# Active_Sensor_BB.net
KiCad netlist of a schematic drawn in Altium Designer
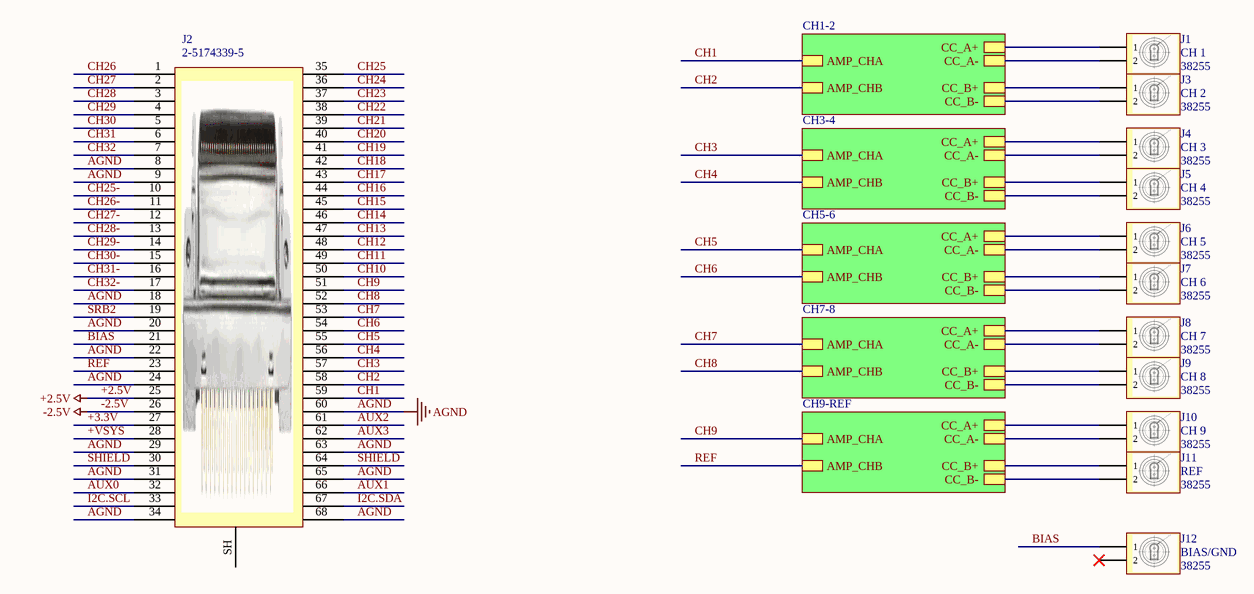
[diagram p0: Active Sensor BB.SchDoc]

(export (version "E")
  (design (tool "Eeschema 10.0.6"))
  (components
    (comp (ref "J1")
      (value "CH 1")
      (footprint "38255")
      (fields (field (name "MANUFACTURER") "PLASTICS1") (field (name "MANUFACTURER PART NUMBER") "38255"))
      (libsource (lib "CC BREAKOUT BOARD SCHLIB") (part "38255"))
    )
    (comp (ref "J2")
      (value "10268-6212PC")
      (footprint "2-5174339-5")
      (fields
        (field (name "MANUFACTURER") "TE Connectivity")
        (field (name "MANUFACTURER PART NUMBER") "2-5174339-5")
      )
      (libsource (lib "LUCHADOR SCHLIB") (part "10268-6212PC"))
    )
    (comp (ref "J3")
      (value "CH 2")
      (footprint "38255")
      (fields (field (name "MANUFACTURER") "PLASTICS1") (field (name "MANUFACTURER PART NUMBER") "38255"))
      (libsource (lib "CC BREAKOUT BOARD SCHLIB") (part "38255"))
    )
    (comp (ref "J4")
      (value "CH 3")
      (footprint "38255")
      (fields (field (name "MANUFACTURER") "PLASTICS1") (field (name "MANUFACTURER PART NUMBER") "38255"))
      (libsource (lib "CC BREAKOUT BOARD SCHLIB") (part "38255"))
    )
    (comp (ref "J5")
      (value "CH 4")
      (footprint "38255")
      (fields (field (name "MANUFACTURER") "PLASTICS1") (field (name "MANUFACTURER PART NUMBER") "38255"))
      (libsource (lib "CC BREAKOUT BOARD SCHLIB") (part "38255"))
    )
    (comp (ref "J6")
      (value "CH 5")
      (footprint "38255")
      (fields (field (name "MANUFACTURER") "PLASTICS1") (field (name "MANUFACTURER PART NUMBER") "38255"))
      (libsource (lib "CC BREAKOUT BOARD SCHLIB") (part "38255"))
    )
    (comp (ref "J7")
      (value "CH 6")
      (footprint "38255")
      (fields (field (name "MANUFACTURER") "PLASTICS1") (field (name "MANUFACTURER PART NUMBER") "38255"))
      (libsource (lib "CC BREAKOUT BOARD SCHLIB") (part "38255"))
    )
    (comp (ref "J8")
      (value "CH 7")
      (footprint "38255")
      (fields (field (name "MANUFACTURER") "PLASTICS1") (field (name "MANUFACTURER PART NUMBER") "38255"))
      (libsource (lib "CC BREAKOUT BOARD SCHLIB") (part "38255"))
    )
    (comp (ref "J9")
      (value "CH 8")
      (footprint "38255")
      (fields (field (name "MANUFACTURER") "PLASTICS1") (field (name "MANUFACTURER PART NUMBER") "38255"))
      (libsource (lib "CC BREAKOUT BOARD SCHLIB") (part "38255"))
    )
    (comp (ref "J10")
      (value "CH 9")
      (footprint "38255")
      (fields (field (name "MANUFACTURER") "PLASTICS1") (field (name "MANUFACTURER PART NUMBER") "38255"))
      (libsource (lib "CC BREAKOUT BOARD SCHLIB") (part "38255"))
    )
    (comp (ref "J11")
      (value "REF")
      (footprint "38255")
      (fields (field (name "MANUFACTURER") "PLASTICS1") (field (name "MANUFACTURER PART NUMBER") "38255"))
      (libsource (lib "CC BREAKOUT BOARD SCHLIB") (part "38255"))
    )
    (comp (ref "J12")
      (value "BIAS/GND")
      (footprint "38255")
      (fields (field (name "MANUFACTURER") "PLASTICS1") (field (name "MANUFACTURER PART NUMBER") "38255"))
      (libsource (lib "CC BREAKOUT BOARD SCHLIB") (part "38255"))
    )
  )
  (nets
    (net (code "1") (name "+2.5V") (class "Default")
      (node (ref "J2") (pin "25") (pinfunction "25_25") (pintype "passive"))
    )
    (net (code "2") (name "-2.5V") (class "Default")
      (node (ref "J2") (pin "26") (pinfunction "26_26") (pintype "passive"))
    )
    (net (code "3") (name "/+3.3V") (class "Default")
      (node (ref "J2") (pin "27") (pinfunction "27_27") (pintype "passive"))
    )
    (net (code "4") (name "/+VSYS") (class "Default")
      (node (ref "J2") (pin "28") (pinfunction "28_28") (pintype "passive"))
    )
    (net (code "5") (name "/AUX0") (class "Default")
      (node (ref "J2") (pin "32") (pinfunction "32_32") (pintype "passive"))
    )
    (net (code "6") (name "/AUX1") (class "Default")
      (node (ref "J2") (pin "66") (pinfunction "66_66") (pintype "passive"))
    )
    (net (code "7") (name "/AUX2") (class "Default")
      (node (ref "J2") (pin "61") (pinfunction "61_61") (pintype "passive"))
    )
    (net (code "8") (name "/AUX3") (class "Default")
      (node (ref "J2") (pin "62") (pinfunction "62_62") (pintype "passive"))
    )
    (net (code "9") (name "/BIAS") (class "Default")
      (node (ref "J12") (pin "1") (pinfunction "1_1") (pintype "passive"))
      (node (ref "J2") (pin "21") (pinfunction "21_21") (pintype "passive"))
    )
    (net (code "10") (name "/CC_A+") (class "Default")
      (node (ref "J10") (pin "1") (pinfunction "1_1") (pintype "passive"))
    )
    (net (code "11") (name "/CC_A+_1") (class "Default")
      (node (ref "J1") (pin "1") (pinfunction "1_1") (pintype "passive"))
    )
    (net (code "12") (name "/CC_A+_2") (class "Default")
      (node (ref "J4") (pin "1") (pinfunction "1_1") (pintype "passive"))
    )
    (net (code "13") (name "/CC_A+_3") (class "Default")
      (node (ref "J6") (pin "1") (pinfunction "1_1") (pintype "passive"))
    )
    (net (code "14") (name "/CC_A+_4") (class "Default")
      (node (ref "J8") (pin "1") (pinfunction "1_1") (pintype "passive"))
    )
    (net (code "15") (name "/CC_A-") (class "Default")
      (node (ref "J10") (pin "2") (pinfunction "2_2") (pintype "passive"))
    )
    (net (code "16") (name "/CC_A-_1") (class "Default")
      (node (ref "J1") (pin "2") (pinfunction "2_2") (pintype "passive"))
    )
    (net (code "17") (name "/CC_A-_2") (class "Default")
      (node (ref "J4") (pin "2") (pinfunction "2_2") (pintype "passive"))
    )
    (net (code "18") (name "/CC_A-_3") (class "Default")
      (node (ref "J6") (pin "2") (pinfunction "2_2") (pintype "passive"))
    )
    (net (code "19") (name "/CC_A-_4") (class "Default")
      (node (ref "J8") (pin "2") (pinfunction "2_2") (pintype "passive"))
    )
    (net (code "20") (name "/CC_B+") (class "Default")
      (node (ref "J11") (pin "1") (pinfunction "1_1") (pintype "passive"))
    )
    (net (code "21") (name "/CC_B+_1") (class "Default")
      (node (ref "J3") (pin "1") (pinfunction "1_1") (pintype "passive"))
    )
    (net (code "22") (name "/CC_B+_2") (class "Default")
      (node (ref "J5") (pin "1") (pinfunction "1_1") (pintype "passive"))
    )
    (net (code "23") (name "/CC_B+_3") (class "Default")
      (node (ref "J7") (pin "1") (pinfunction "1_1") (pintype "passive"))
    )
    (net (code "24") (name "/CC_B+_4") (class "Default")
      (node (ref "J9") (pin "1") (pinfunction "1_1") (pintype "passive"))
    )
    (net (code "25") (name "/CC_B-") (class "Default")
      (node (ref "J9") (pin "2") (pinfunction "2_2") (pintype "passive"))
    )
    (net (code "26") (name "/CC_B-_1") (class "Default")
      (node (ref "J11") (pin "2") (pinfunction "2_2") (pintype "passive"))
    )
    (net (code "27") (name "/CC_B-_2") (class "Default")
      (node (ref "J3") (pin "2") (pinfunction "2_2") (pintype "passive"))
    )
    (net (code "28") (name "/CC_B-_3") (class "Default")
      (node (ref "J5") (pin "2") (pinfunction "2_2") (pintype "passive"))
    )
    (net (code "29") (name "/CC_B-_4") (class "Default")
      (node (ref "J7") (pin "2") (pinfunction "2_2") (pintype "passive"))
    )
    (net (code "30") (name "/CH1") (class "Default")
      (node (ref "J2") (pin "59") (pinfunction "59_59") (pintype "passive"))
    )
    (net (code "31") (name "/CH2") (class "Default")
      (node (ref "J2") (pin "58") (pinfunction "58_58") (pintype "passive"))
    )
    (net (code "32") (name "/CH3") (class "Default")
      (node (ref "J2") (pin "57") (pinfunction "57_57") (pintype "passive"))
    )
    (net (code "33") (name "/CH4") (class "Default")
      (node (ref "J2") (pin "56") (pinfunction "56_56") (pintype "passive"))
    )
    (net (code "34") (name "/CH5") (class "Default")
      (node (ref "J2") (pin "55") (pinfunction "55_55") (pintype "passive"))
    )
    (net (code "35") (name "/CH6") (class "Default")
      (node (ref "J2") (pin "54") (pinfunction "54_54") (pintype "passive"))
    )
    (net (code "36") (name "/CH7") (class "Default")
      (node (ref "J2") (pin "53") (pinfunction "53_53") (pintype "passive"))
    )
    (net (code "37") (name "/CH8") (class "Default")
      (node (ref "J2") (pin "52") (pinfunction "52_52") (pintype "passive"))
    )
    (net (code "38") (name "/CH9") (class "Default")
      (node (ref "J2") (pin "51") (pinfunction "51_51") (pintype "passive"))
    )
    (net (code "39") (name "/CH10") (class "Default")
      (node (ref "J2") (pin "50") (pinfunction "50_50") (pintype "passive"))
    )
    (net (code "40") (name "/CH11") (class "Default")
      (node (ref "J2") (pin "49") (pinfunction "49_49") (pintype "passive"))
    )
    (net (code "41") (name "/CH12") (class "Default")
      (node (ref "J2") (pin "48") (pinfunction "48_48") (pintype "passive"))
    )
    (net (code "42") (name "/CH13") (class "Default")
      (node (ref "J2") (pin "47") (pinfunction "47_47") (pintype "passive"))
    )
    (net (code "43") (name "/CH14") (class "Default")
      (node (ref "J2") (pin "46") (pinfunction "46_46") (pintype "passive"))
    )
    (net (code "44") (name "/CH15") (class "Default")
      (node (ref "J2") (pin "45") (pinfunction "45_45") (pintype "passive"))
    )
    (net (code "45") (name "/CH16") (class "Default")
      (node (ref "J2") (pin "44") (pinfunction "44_44") (pintype "passive"))
    )
    (net (code "46") (name "/CH17") (class "Default")
      (node (ref "J2") (pin "43") (pinfunction "43_43") (pintype "passive"))
    )
    (net (code "47") (name "/CH18") (class "Default")
      (node (ref "J2") (pin "42") (pinfunction "42_42") (pintype "passive"))
    )
    (net (code "48") (name "/CH19") (class "Default")
      (node (ref "J2") (pin "41") (pinfunction "41_41") (pintype "passive"))
    )
    (net (code "49") (name "/CH20") (class "Default")
      (node (ref "J2") (pin "40") (pinfunction "40_40") (pintype "passive"))
    )
    (net (code "50") (name "/CH21") (class "Default")
      (node (ref "J2") (pin "39") (pinfunction "39_39") (pintype "passive"))
    )
    (net (code "51") (name "/CH22") (class "Default")
      (node (ref "J2") (pin "38") (pinfunction "38_38") (pintype "passive"))
    )
    (net (code "52") (name "/CH23") (class "Default")
      (node (ref "J2") (pin "37") (pinfunction "37_37") (pintype "passive"))
    )
    (net (code "53") (name "/CH24") (class "Default")
      (node (ref "J2") (pin "36") (pinfunction "36_36") (pintype "passive"))
    )
    (net (code "54") (name "/CH25") (class "Default")
      (node (ref "J2") (pin "35") (pinfunction "35_35") (pintype "passive"))
    )
    (net (code "55") (name "/CH25-") (class "Default")
      (node (ref "J2") (pin "10") (pinfunction "10_10") (pintype "passive"))
    )
    (net (code "56") (name "/CH26") (class "Default")
      (node (ref "J2") (pin "1") (pinfunction "1_1") (pintype "passive"))
    )
    (net (code "57") (name "/CH26-") (class "Default")
      (node (ref "J2") (pin "11") (pinfunction "11_11") (pintype "passive"))
    )
    (net (code "58") (name "/CH27") (class "Default")
      (node (ref "J2") (pin "2") (pinfunction "2_2") (pintype "passive"))
    )
    (net (code "59") (name "/CH27-") (class "Default")
      (node (ref "J2") (pin "12") (pinfunction "12_12") (pintype "passive"))
    )
    (net (code "60") (name "/CH28") (class "Default")
      (node (ref "J2") (pin "3") (pinfunction "3_3") (pintype "passive"))
    )
    (net (code "61") (name "/CH28-") (class "Default")
      (node (ref "J2") (pin "13") (pinfunction "13_13") (pintype "passive"))
    )
    (net (code "62") (name "/CH29") (class "Default")
      (node (ref "J2") (pin "4") (pinfunction "4_4") (pintype "passive"))
    )
    (net (code "63") (name "/CH29-") (class "Default")
      (node (ref "J2") (pin "14") (pinfunction "14_14") (pintype "passive"))
    )
    (net (code "64") (name "/CH30") (class "Default")
      (node (ref "J2") (pin "5") (pinfunction "5_5") (pintype "passive"))
    )
    (net (code "65") (name "/CH30-") (class "Default")
      (node (ref "J2") (pin "15") (pinfunction "15_15") (pintype "passive"))
    )
    (net (code "66") (name "/CH31") (class "Default")
      (node (ref "J2") (pin "6") (pinfunction "6_6") (pintype "passive"))
    )
    (net (code "67") (name "/CH31-") (class "Default")
      (node (ref "J2") (pin "16") (pinfunction "16_16") (pintype "passive"))
    )
    (net (code "68") (name "/CH32") (class "Default")
      (node (ref "J2") (pin "7") (pinfunction "7_7") (pintype "passive"))
    )
    (net (code "69") (name "/CH32-") (class "Default")
      (node (ref "J2") (pin "17") (pinfunction "17_17") (pintype "passive"))
    )
    (net (code "70") (name "/I2C.SCL") (class "Default")
      (node (ref "J2") (pin "33") (pinfunction "33_33") (pintype "passive"))
    )
    (net (code "71") (name "/I2C.SDA") (class "Default")
      (node (ref "J2") (pin "67") (pinfunction "67_67") (pintype "passive"))
    )
    (net (code "72") (name "/REF") (class "Default")
      (node (ref "J2") (pin "23") (pinfunction "23_23") (pintype "passive"))
    )
    (net (code "73") (name "/SHIELD") (class "Default")
      (node (ref "J2") (pin "30") (pinfunction "30_30") (pintype "passive"))
      (node (ref "J2") (pin "64") (pinfunction "64_64") (pintype "passive"))
    )
    (net (code "74") (name "/SRB2") (class "Default")
      (node (ref "J2") (pin "19") (pinfunction "19_19") (pintype "passive"))
    )
    (net (code "75") (name "AGND") (class "Default")
      (node (ref "J2") (pin "18") (pinfunction "18_18") (pintype "passive"))
      (node (ref "J2") (pin "20") (pinfunction "20_20") (pintype "passive"))
      (node (ref "J2") (pin "22") (pinfunction "22_22") (pintype "passive"))
      (node (ref "J2") (pin "24") (pinfunction "24_24") (pintype "passive"))
      (node (ref "J2") (pin "29") (pinfunction "29_29") (pintype "passive"))
      (node (ref "J2") (pin "31") (pinfunction "31_31") (pintype "passive"))
      (node (ref "J2") (pin "34") (pinfunction "34_34") (pintype "passive"))
      (node (ref "J2") (pin "60") (pinfunction "60_60") (pintype "passive"))
      (node (ref "J2") (pin "63") (pinfunction "63_63") (pintype "passive"))
      (node (ref "J2") (pin "65") (pinfunction "65_65") (pintype "passive"))
      (node (ref "J2") (pin "68") (pinfunction "68_68") (pintype "passive"))
      (node (ref "J2") (pin "8") (pinfunction "8_8") (pintype "passive"))
      (node (ref "J2") (pin "9") (pinfunction "9_9") (pintype "passive"))
    )
    (net (code "76") (name "unconnected-(J2-PadSH)") (class "Default")
      (node (ref "J2") (pin "SH") (pinfunction "SH_SH") (pintype "passive"))
    )
    (net (code "77") (name "unconnected-(J12-Pad2)") (class "Default")
      (node (ref "J12") (pin "2") (pinfunction "2_2") (pintype "passive+no_connect"))
    )
  )
)
